# TempAdc.net
KiCad netlist of a schematic drawn in Altium Designer
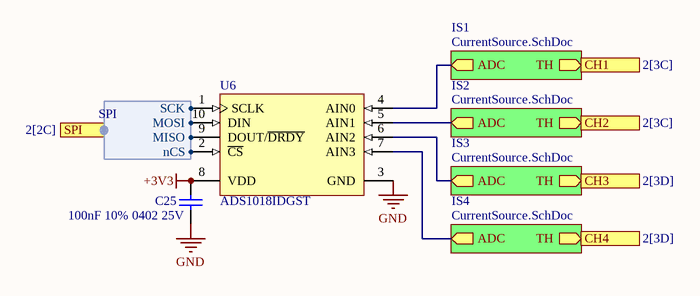
[diagram p0: TempAdc.SchDoc]

(export (version "E")
  (design (tool "Eeschema 10.0.6"))
  (components
    (comp (ref "C25")
      (value "100nF 10% 0402 25V")
      (footprint "0402N")
      (fields (field (name "TOLERANCE") "10") (field (name "VOLTAGE") "25"))
      (libsource (lib "MiscPassives") (part "C0402"))
    )
    (comp (ref "U6")
      (value "ADS1018IDGST")
      (footprint "TI-DGS10_N")
      (fields (field (name "MANUFACTURER") "Texas Instruments"))
      (libsource (lib "Altium Content Vault") (part "TI-ADS1X18XXX10"))
    )
  )
  (nets
    (net (code "2") (name "+3V3") (class "Default")
      (node (ref "C25") (pin "2") (pinfunction "2_2") (pintype "passive"))
      (node (ref "U6") (pin "8") (pinfunction "VDD_8") (pintype "power_in"))
    )
    (net (code "3") (name "/ADC") (class "Default")
      (node (ref "U6") (pin "5") (pinfunction "AIN1_5") (pintype "input"))
    )
    (net (code "4") (name "/ADC_1") (class "Default")
      (node (ref "U6") (pin "7") (pinfunction "AIN3_7") (pintype "input"))
    )
    (net (code "5") (name "/ADC_2") (class "Default")
      (node (ref "U6") (pin "6") (pinfunction "AIN2_6") (pintype "input"))
    )
    (net (code "6") (name "/ADC_3") (class "Default")
      (node (ref "U6") (pin "4") (pinfunction "AIN0_4") (pintype "input"))
    )
    (net (code "12") (name "GND") (class "Default")
      (node (ref "C25") (pin "1") (pinfunction "1_1") (pintype "passive"))
      (node (ref "U6") (pin "3") (pinfunction "GND_3") (pintype "power_in"))
    )
    (net (code "13") (name "unconnected-(U6-DIN-Pad10)") (class "Default")
      (node (ref "U6") (pin "10") (pinfunction "DIN_10") (pintype "input"))
    )
    (net (code "14") (name "unconnected-(U6-DOUT{slash}~{DRDY}-Pad9)") (class "Default")
      (node (ref "U6") (pin "9") (pinfunction "DOUT/~{DRDY}_9") (pintype "tri_state"))
    )
    (net (code "15") (name "unconnected-(U6-SCLK-Pad1)") (class "Default")
      (node (ref "U6") (pin "1") (pinfunction "SCLK_1") (pintype "input"))
    )
    (net (code "16") (name "unconnected-(U6-~{CS}-Pad2)") (class "Default")
      (node (ref "U6") (pin "2") (pinfunction "~{CS}_2") (pintype "input"))
    )
  )
)
